# controller14.net
KiCad netlist of a schematic drawn in EAGLE
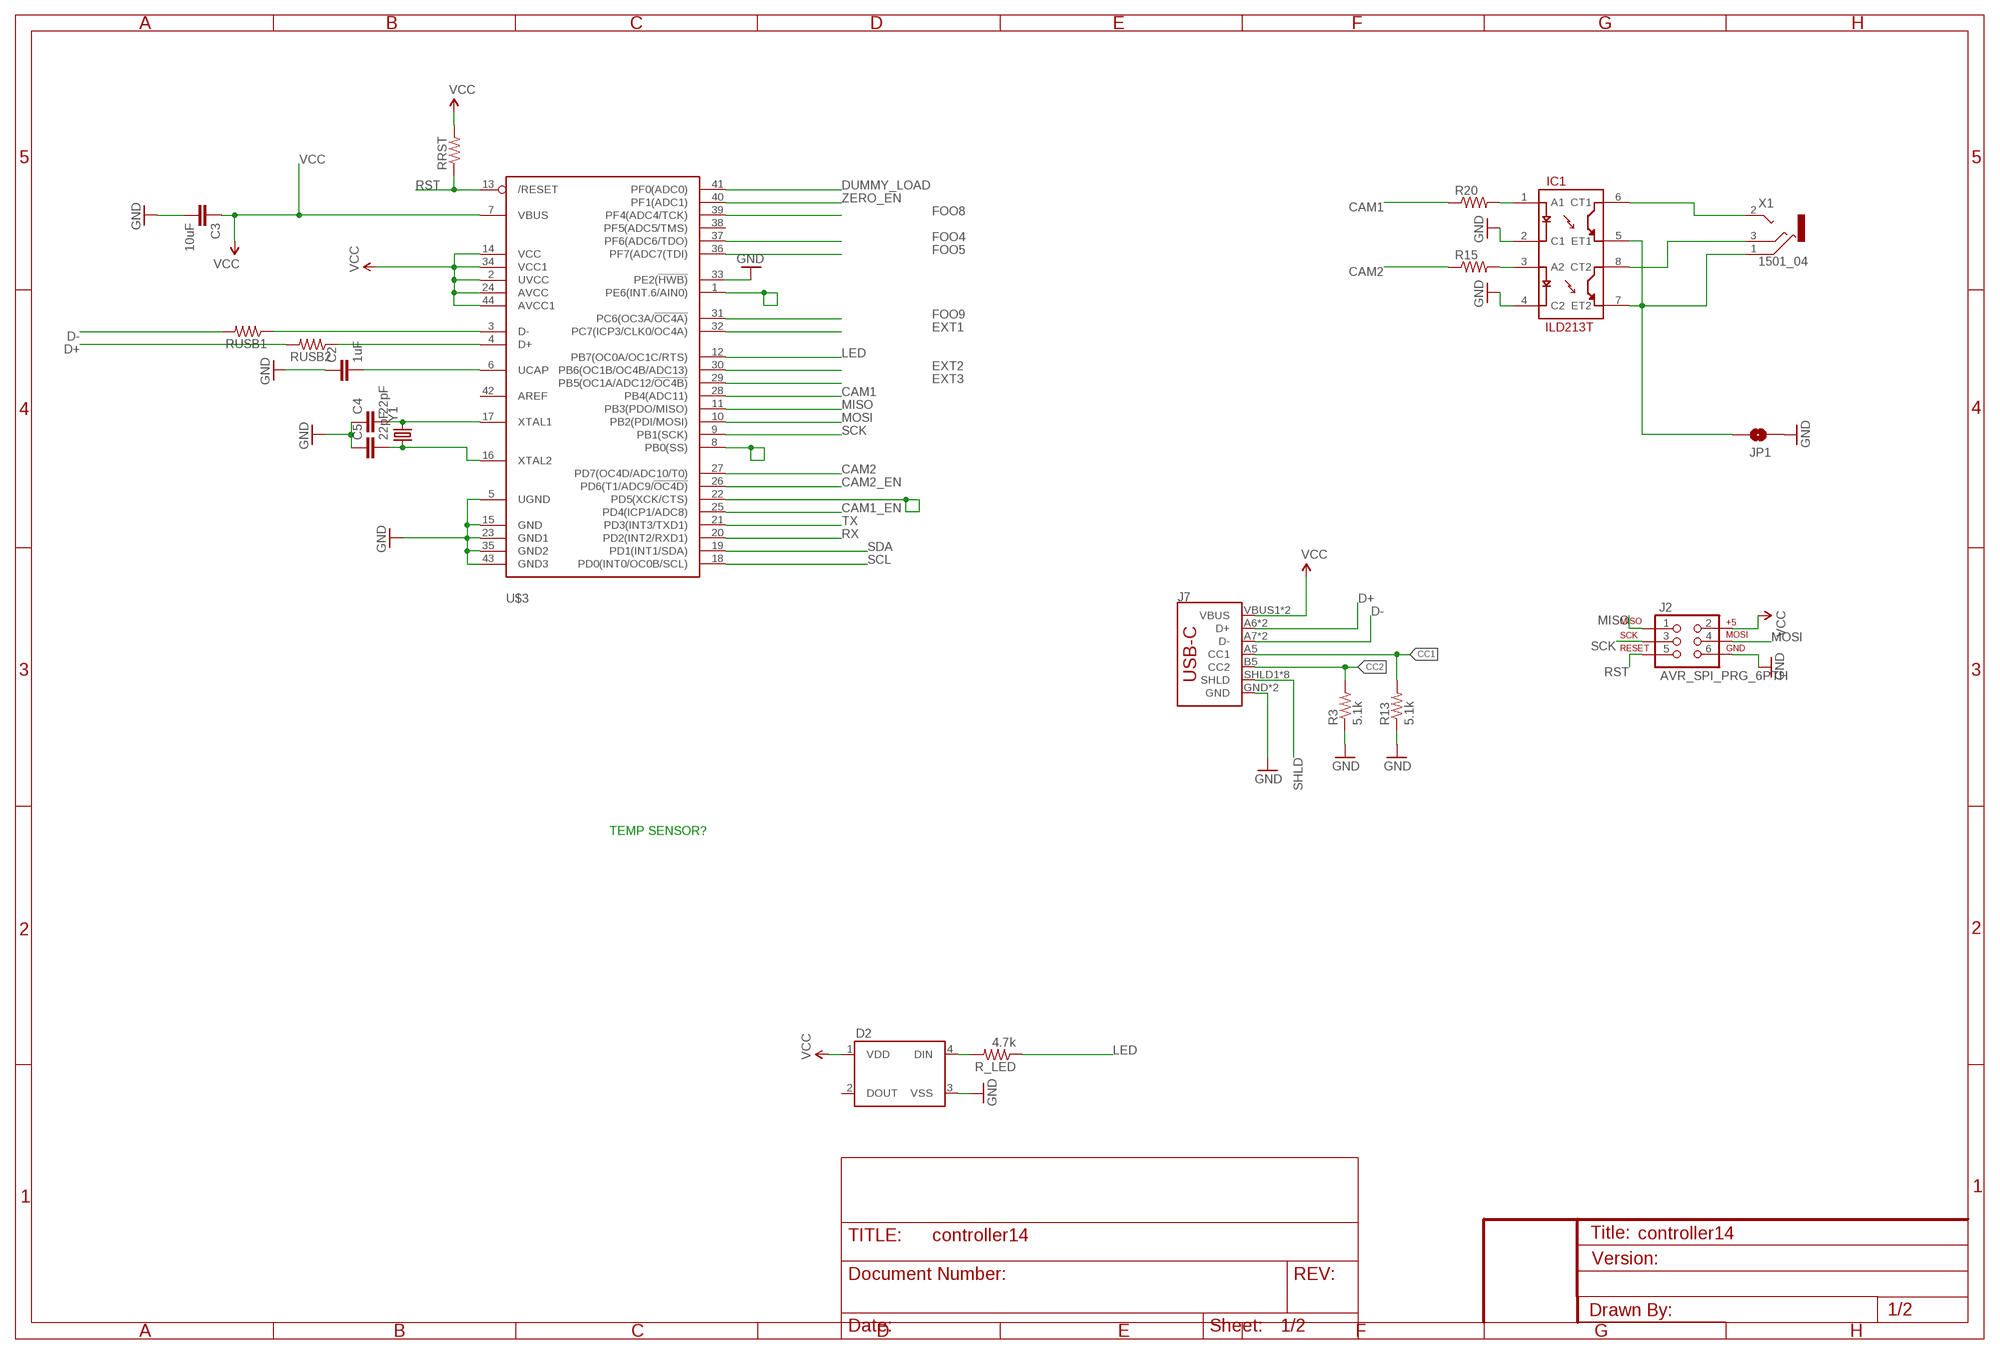
[diagram p0: schematic, sheet 1]
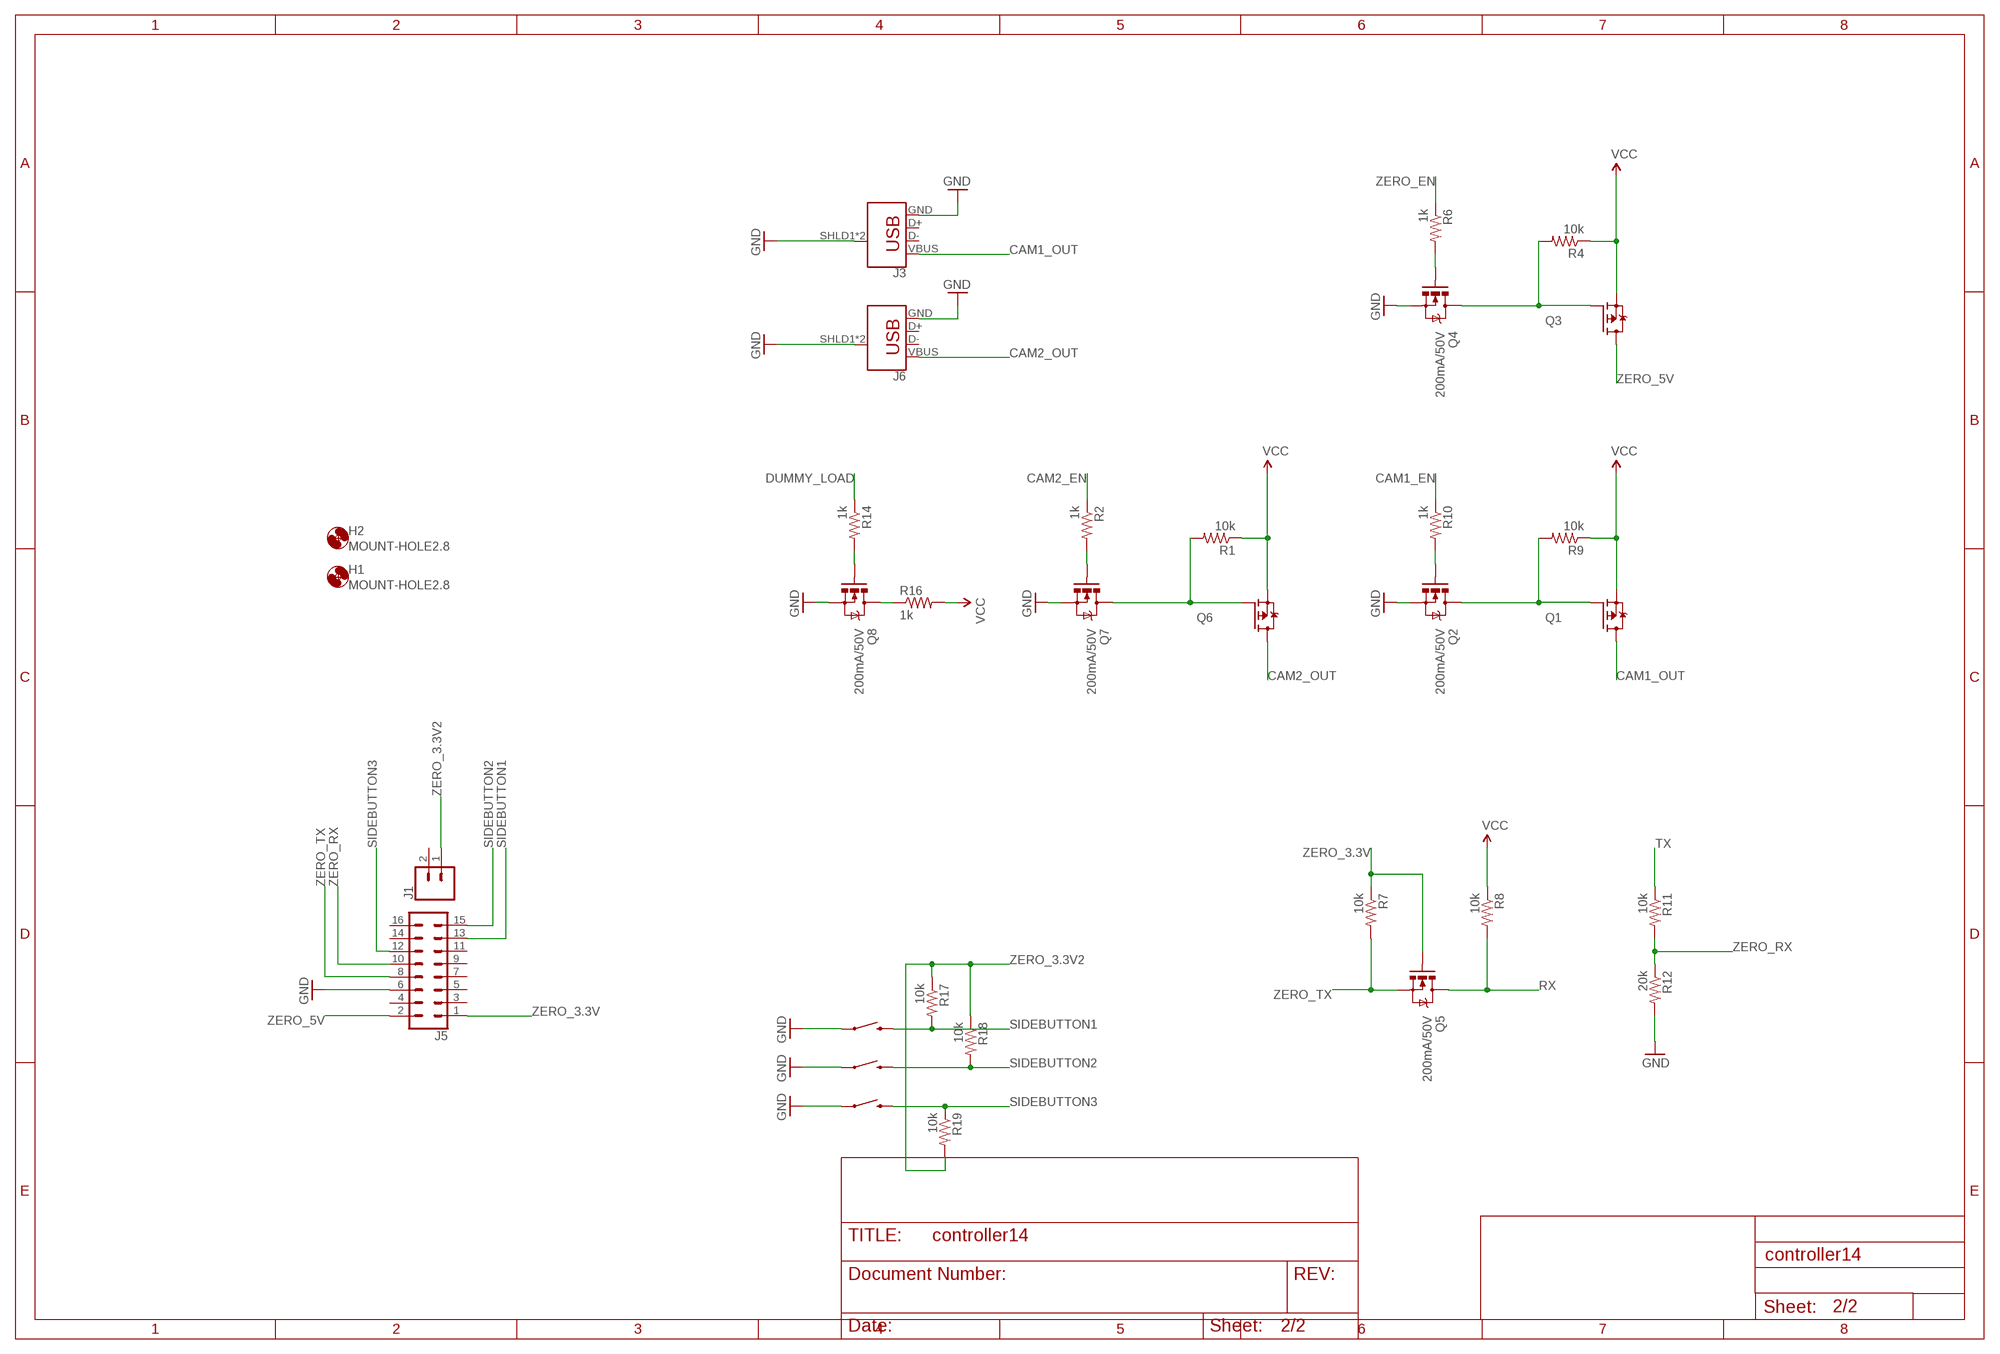
[diagram p1: schematic, sheet 2]

(export (version "E")
  (design (tool "Eeschema 10.0.6"))
  (components
    (comp (ref "C2")
      (value "1uF")
      (footprint "eagle-import:1206")
      (libsource (lib "eagle-import") (part "CAP1206"))
    )
    (comp (ref "C3")
      (value "10uF")
      (footprint "eagle-import:1206")
      (libsource (lib "eagle-import") (part "SparkFun-Passives_CAP1206"))
    )
    (comp (ref "C4")
      (value "22pF")
      (footprint "eagle-import:1206")
      (libsource (lib "eagle-import") (part "SparkFun-Passives_CAP1206"))
    )
    (comp (ref "C5")
      (value "22pF")
      (footprint "eagle-import:1206")
      (libsource (lib "eagle-import") (part "SparkFun-Passives_CAP1206"))
    )
    (comp (ref "D2")
      (value "WS2812B")
      (footprint "eagle-import:WS2812B")
      (libsource (lib "eagle-import") (part "WS2812B"))
    )
    (comp (ref "IC1")
      (value "ILD213T")
      (footprint "eagle-import:SO08")
      (libsource (lib "eagle-import") (part "ILD213T"))
    )
    (comp (ref "J2")
      (value "AVR_SPI_PRG_6PTH")
      (footprint "eagle-import:2X3")
      (libsource (lib "eagle-import") (part "AVR_SPI_PRG_6PTH"))
    )
    (comp (ref "J7")
      (value "USB_C16PIN")
      (footprint "eagle-import:USB-C-16P")
      (libsource (lib "eagle-import") (part "USB_C16PIN"))
    )
    (comp (ref "JP1")
      (value "JUMPER-PAD-2-NOYES_SILK")
      (footprint "eagle-import:PAD-JUMPER-2-NO_YES_SILK")
      (libsource (lib "eagle-import") (part "JUMPER-PAD-2-NOYES_SILK"))
    )
    (comp (ref "R3")
      (value "5.1k")
      (footprint "eagle-import:1206")
      (libsource (lib "eagle-import") (part "RESISTOR1206"))
    )
    (comp (ref "R13")
      (value "5.1k")
      (footprint "eagle-import:1206")
      (libsource (lib "eagle-import") (part "RESISTOR1206"))
    )
    (comp (ref "R15")
      (value "RESISTOR1206")
      (footprint "eagle-import:1206")
      (libsource (lib "eagle-import") (part "RESISTOR1206"))
    )
    (comp (ref "R20")
      (value "RESISTOR1206")
      (footprint "eagle-import:1206")
      (libsource (lib "eagle-import") (part "RESISTOR1206"))
    )
    (comp (ref "RRST")
      (value "RESISTOR1206")
      (footprint "eagle-import:1206")
      (libsource (lib "eagle-import") (part "RESISTOR1206"))
    )
    (comp (ref "RUSB1")
      (value "RESISTOR1206")
      (footprint "eagle-import:1206")
      (libsource (lib "eagle-import") (part "RESISTOR1206"))
    )
    (comp (ref "RUSB2")
      (value "RESISTOR1206")
      (footprint "eagle-import:1206")
      (libsource (lib "eagle-import") (part "RESISTOR1206"))
    )
    (comp (ref "R_LED")
      (value "4.7k")
      (footprint "eagle-import:1206")
      (libsource (lib "eagle-import") (part "SparkFun-Resistors_RESISTOR1206"))
    )
    (comp (ref "U$3")
      (value "ATMEGA32U4-AU")
      (footprint "eagle-import:TQFP44")
      (libsource (lib "eagle-import") (part "ATMEGA32U4-AU"))
    )
    (comp (ref "X1")
      (value "1501_04")
      (footprint "eagle-import:1501_05")
      (libsource (lib "eagle-import") (part "1501_04"))
    )
    (comp (ref "Y1")
      (value "CRYSTALCRYSTAL-SMD-5X3-16MHZ")
      (footprint "eagle-import:CRYSTAL-SMD-5X3")
      (libsource (lib "eagle-import") (part "CRYSTALCRYSTAL-SMD-5X3-16MHZ"))
    )
    (comp (ref "H1")
      (value "MOUNT-HOLE2.8")
      (footprint "eagle-import:2,8")
      (libsource (lib "eagle-import") (part "MOUNT-HOLE2.8"))
    )
    (comp (ref "H2")
      (value "MOUNT-HOLE2.8")
      (footprint "eagle-import:2,8")
      (libsource (lib "eagle-import") (part "MOUNT-HOLE2.8"))
    )
    (comp (ref "J1")
      (value "CONN_02")
      (footprint "eagle-import:1X02")
      (libsource (lib "eagle-import") (part "CONN_02"))
    )
    (comp (ref "J3")
      (value "USB_A_SMT_FEMALE")
      (footprint "eagle-import:USB-A-S-SILK-FEMALE")
      (libsource (lib "eagle-import") (part "USB_A_SMT_FEMALE"))
    )
    (comp (ref "J5")
      (value "CONN_08X2")
      (footprint "eagle-import:2X8")
      (libsource (lib "eagle-import") (part "CONN_08X2"))
    )
    (comp (ref "J6")
      (value "USB_A_SMT_FEMALE")
      (footprint "eagle-import:USB-A-S-SILK-FEMALE")
      (libsource (lib "eagle-import") (part "USB_A_SMT_FEMALE"))
    )
    (comp (ref "Q1")
      (value "FDD4141TO252")
      (footprint "eagle-import:TO252")
      (libsource (lib "eagle-import") (part "FDD4141TO252"))
    )
    (comp (ref "Q2")
      (value "200mA/50V")
      (footprint "eagle-import:SOT23-3")
      (libsource (lib "eagle-import") (part "MOSFET-NCHANNELBSS138"))
    )
    (comp (ref "Q3")
      (value "FDD4141TO252")
      (footprint "eagle-import:TO252")
      (libsource (lib "eagle-import") (part "FDD4141TO252"))
    )
    (comp (ref "Q4")
      (value "200mA/50V")
      (footprint "eagle-import:SOT23-3")
      (libsource (lib "eagle-import") (part "MOSFET-NCHANNELBSS138"))
    )
    (comp (ref "Q5")
      (value "200mA/50V")
      (footprint "eagle-import:SOT23-3")
      (libsource (lib "eagle-import") (part "MOSFET-NCHANNELBSS138"))
    )
    (comp (ref "Q6")
      (value "FDD4141TO252")
      (footprint "eagle-import:TO252")
      (libsource (lib "eagle-import") (part "FDD4141TO252"))
    )
    (comp (ref "Q7")
      (value "200mA/50V")
      (footprint "eagle-import:SOT23-3")
      (libsource (lib "eagle-import") (part "MOSFET-NCHANNELBSS138"))
    )
    (comp (ref "Q8")
      (value "200mA/50V")
      (footprint "eagle-import:SOT23-3")
      (libsource (lib "eagle-import") (part "MOSFET-NCHANNELBSS138"))
    )
    (comp (ref "R1")
      (value "10k")
      (footprint "eagle-import:1206")
      (libsource (lib "eagle-import") (part "SparkFun-Resistors_RESISTOR1206"))
    )
    (comp (ref "R2")
      (value "1k")
      (footprint "eagle-import:1206")
      (libsource (lib "eagle-import") (part "SparkFun-Resistors_RESISTOR1206"))
    )
    (comp (ref "R4")
      (value "10k")
      (footprint "eagle-import:1206")
      (libsource (lib "eagle-import") (part "SparkFun-Resistors_RESISTOR1206"))
    )
    (comp (ref "R6")
      (value "1k")
      (footprint "eagle-import:1206")
      (libsource (lib "eagle-import") (part "SparkFun-Resistors_RESISTOR1206"))
    )
    (comp (ref "R7")
      (value "10k")
      (footprint "eagle-import:1206")
      (libsource (lib "eagle-import") (part "SparkFun-Resistors_RESISTOR1206"))
    )
    (comp (ref "R8")
      (value "10k")
      (footprint "eagle-import:1206")
      (libsource (lib "eagle-import") (part "SparkFun-Resistors_RESISTOR1206"))
    )
    (comp (ref "R9")
      (value "10k")
      (footprint "eagle-import:1206")
      (libsource (lib "eagle-import") (part "SparkFun-Resistors_RESISTOR1206"))
    )
    (comp (ref "R10")
      (value "1k")
      (footprint "eagle-import:1206")
      (libsource (lib "eagle-import") (part "SparkFun-Resistors_RESISTOR1206"))
    )
    (comp (ref "R11")
      (value "10k")
      (footprint "eagle-import:1206")
      (libsource (lib "eagle-import") (part "SparkFun-Resistors_RESISTOR1206"))
    )
    (comp (ref "R12")
      (value "20k")
      (footprint "eagle-import:1206")
      (libsource (lib "eagle-import") (part "SparkFun-Resistors_RESISTOR1206"))
    )
    (comp (ref "R14")
      (value "1k")
      (footprint "eagle-import:1206")
      (libsource (lib "eagle-import") (part "SparkFun-Resistors_RESISTOR1206"))
    )
    (comp (ref "R16")
      (value "1k")
      (footprint "eagle-import:1206")
      (libsource (lib "eagle-import") (part "SparkFun-Resistors_RESISTOR1206"))
    )
    (comp (ref "R17")
      (value "10k")
      (footprint "eagle-import:1206")
      (libsource (lib "eagle-import") (part "SparkFun-Resistors_RESISTOR1206"))
    )
    (comp (ref "R18")
      (value "10k")
      (footprint "eagle-import:1206")
      (libsource (lib "eagle-import") (part "SparkFun-Resistors_RESISTOR1206"))
    )
    (comp (ref "R19")
      (value "10k")
      (footprint "eagle-import:1206")
      (libsource (lib "eagle-import") (part "SparkFun-Resistors_RESISTOR1206"))
    )
    (comp (ref "S3")
      (value "MOMENTARY-SWITCH-SPST-PTH-RIGHT-ANGLE-KIT")
      (footprint "eagle-import:TACTILE_SWITCH_PTH_RIGHT_ANGLE_KIT")
      (libsource (lib "eagle-import") (part "MOMENTARY-SWITCH-SPST-PTH-RIGHT-ANGLE-KIT"))
    )
    (comp (ref "S4")
      (value "MOMENTARY-SWITCH-SPST-PTH-RIGHT-ANGLE-KIT")
      (footprint "eagle-import:TACTILE_SWITCH_PTH_RIGHT_ANGLE_KIT")
      (libsource (lib "eagle-import") (part "MOMENTARY-SWITCH-SPST-PTH-RIGHT-ANGLE-KIT"))
    )
    (comp (ref "S5")
      (value "MOMENTARY-SWITCH-SPST-PTH-RIGHT-ANGLE-KIT")
      (footprint "eagle-import:TACTILE_SWITCH_PTH_RIGHT_ANGLE_KIT")
      (libsource (lib "eagle-import") (part "MOMENTARY-SWITCH-SPST-PTH-RIGHT-ANGLE-KIT"))
    )
  )
  (nets
    (net (code "1") (name "CAM1") (class "Default")
      (node (ref "R20") (pin "1") (pinfunction "1_1") (pintype "passive"))
      (node (ref "U$3") (pin "28") (pinfunction "PB4(ADC11)_28") (pintype "bidirectional"))
    )
    (net (code "2") (name "CAM1_EN") (class "Default")
      (node (ref "R10") (pin "1") (pinfunction "1_1") (pintype "passive"))
      (node (ref "U$3") (pin "25") (pinfunction "PD4(ICP1/ADC8)_25") (pintype "bidirectional"))
    )
    (net (code "3") (name "CAM1_OUT") (class "Default")
      (node (ref "J3") (pin "VBUS") (pinfunction "VBUS_VBUS") (pintype "power_in"))
      (node (ref "Q1") (pin "3") (pinfunction "D_3") (pintype "passive"))
    )
    (net (code "4") (name "CAM2") (class "Default")
      (node (ref "R15") (pin "1") (pinfunction "1_1") (pintype "passive"))
      (node (ref "U$3") (pin "27") (pinfunction "PD7(OC4D/ADC10/T0)_27") (pintype "bidirectional"))
    )
    (net (code "5") (name "CAM2_EN") (class "Default")
      (node (ref "R2") (pin "1") (pinfunction "1_1") (pintype "passive"))
      (node (ref "U$3") (pin "26") (pinfunction "PD6(T1/ADC9/~{OC4D})_26") (pintype "bidirectional"))
    )
    (net (code "6") (name "CAM2_OUT") (class "Default")
      (node (ref "J6") (pin "VBUS") (pinfunction "VBUS_VBUS") (pintype "power_in"))
      (node (ref "Q6") (pin "3") (pinfunction "D_3") (pintype "passive"))
    )
    (net (code "7") (name "CC1") (class "Default")
      (node (ref "J7") (pin "A5") (pinfunction "CC1_A5") (pintype "bidirectional"))
      (node (ref "R13") (pin "2") (pinfunction "2_2") (pintype "passive"))
    )
    (net (code "8") (name "CC2") (class "Default")
      (node (ref "J7") (pin "B5") (pinfunction "CC2_B5") (pintype "bidirectional"))
      (node (ref "R3") (pin "2") (pinfunction "2_2") (pintype "passive"))
    )
    (net (code "9") (name "D+") (class "Default")
      (node (ref "J7") (pin "A6") (pinfunction "D+_A6") (pintype "bidirectional"))
      (node (ref "J7") (pin "B6") (pinfunction "D+_B6") (pintype "bidirectional"))
      (node (ref "RUSB2") (pin "2") (pinfunction "2_2") (pintype "passive"))
    )
    (net (code "10") (name "D-") (class "Default")
      (node (ref "J7") (pin "A7") (pinfunction "D-_A7") (pintype "bidirectional"))
      (node (ref "J7") (pin "B7") (pinfunction "D-_B7") (pintype "bidirectional"))
      (node (ref "RUSB1") (pin "2") (pinfunction "2_2") (pintype "passive"))
    )
    (net (code "11") (name "DUMMY_LOAD") (class "Default")
      (node (ref "R14") (pin "1") (pinfunction "1_1") (pintype "passive"))
      (node (ref "U$3") (pin "41") (pinfunction "PF0(ADC0)_41") (pintype "bidirectional"))
    )
    (net (code "12") (name "EXT1") (class "Default")
      (node (ref "U$3") (pin "32") (pinfunction "PC7(ICP3/CLK0/OC4A)_32") (pintype "bidirectional"))
    )
    (net (code "13") (name "EXT2") (class "Default")
      (node (ref "U$3") (pin "30") (pinfunction "PB6(OC1B/OC4B/ADC13)_30") (pintype "bidirectional"))
    )
    (net (code "14") (name "EXT3") (class "Default")
      (node (ref "U$3") (pin "29") (pinfunction "PB5(OC1A/ADC12/~{OC4B})_29") (pintype "bidirectional"))
    )
    (net (code "15") (name "FOO4") (class "Default")
      (node (ref "U$3") (pin "37") (pinfunction "PF6(ADC6/TDO)_37") (pintype "bidirectional"))
    )
    (net (code "16") (name "FOO5") (class "Default")
      (node (ref "U$3") (pin "36") (pinfunction "PF7(ADC7(TDI)_36") (pintype "bidirectional"))
    )
    (net (code "17") (name "FOO8") (class "Default")
      (node (ref "U$3") (pin "39") (pinfunction "PF4(ADC4/TCK)_39") (pintype "bidirectional"))
    )
    (net (code "18") (name "FOO9") (class "Default")
      (node (ref "U$3") (pin "31") (pinfunction "PC6(OC3A/~{OC4A})_31") (pintype "bidirectional"))
    )
    (net (code "19") (name "GND") (class "Default")
      (node (ref "C2") (pin "1") (pinfunction "1_1") (pintype "passive"))
      (node (ref "C3") (pin "2") (pinfunction "2_2") (pintype "passive"))
      (node (ref "C4") (pin "1") (pinfunction "1_1") (pintype "passive"))
      (node (ref "C5") (pin "1") (pinfunction "1_1") (pintype "passive"))
      (node (ref "D2") (pin "3") (pinfunction "VSS_3") (pintype "power_in"))
      (node (ref "IC1") (pin "2") (pinfunction "C1_2") (pintype "bidirectional"))
      (node (ref "IC1") (pin "4") (pinfunction "C2_4") (pintype "bidirectional"))
      (node (ref "J2") (pin "6") (pinfunction "6_6") (pintype "passive"))
      (node (ref "J3") (pin "GND") (pinfunction "GND_GND") (pintype "power_in"))
      (node (ref "J3") (pin "SHLD1") (pinfunction "SHIELD_SHLD1") (pintype "bidirectional"))
      (node (ref "J3") (pin "SHLD2") (pinfunction "SHIELD_SHLD2") (pintype "bidirectional"))
      (node (ref "J5") (pin "6") (pinfunction "6_6") (pintype "passive"))
      (node (ref "J6") (pin "GND") (pinfunction "GND_GND") (pintype "power_in"))
      (node (ref "J6") (pin "SHLD1") (pinfunction "SHIELD_SHLD1") (pintype "bidirectional"))
      (node (ref "J6") (pin "SHLD2") (pinfunction "SHIELD_SHLD2") (pintype "bidirectional"))
      (node (ref "J7") (pin "GND") (pinfunction "GND_GND") (pintype "bidirectional"))
      (node (ref "J7") (pin "GND2") (pinfunction "GND_GND2") (pintype "bidirectional"))
      (node (ref "JP1") (pin "1") (pinfunction "1_1") (pintype "passive"))
      (node (ref "Q2") (pin "2") (pinfunction "S_2") (pintype "passive"))
      (node (ref "Q4") (pin "2") (pinfunction "S_2") (pintype "passive"))
      (node (ref "Q7") (pin "2") (pinfunction "S_2") (pintype "passive"))
      (node (ref "Q8") (pin "2") (pinfunction "S_2") (pintype "passive"))
      (node (ref "R12") (pin "2") (pinfunction "2_2") (pintype "passive"))
      (node (ref "R13") (pin "1") (pinfunction "1_1") (pintype "passive"))
      (node (ref "R3") (pin "1") (pinfunction "1_1") (pintype "passive"))
      (node (ref "S3") (pin "1") (pinfunction "1_1") (pintype "passive"))
      (node (ref "S4") (pin "1") (pinfunction "1_1") (pintype "passive"))
      (node (ref "S5") (pin "1") (pinfunction "1_1") (pintype "passive"))
      (node (ref "U$3") (pin "15") (pinfunction "GND_15") (pintype "bidirectional"))
      (node (ref "U$3") (pin "23") (pinfunction "GND1_23") (pintype "bidirectional"))
      (node (ref "U$3") (pin "33") (pinfunction "PE2(~{HWB})_33") (pintype "bidirectional"))
      (node (ref "U$3") (pin "35") (pinfunction "GND2_35") (pintype "bidirectional"))
      (node (ref "U$3") (pin "43") (pinfunction "GND3_43") (pintype "bidirectional"))
      (node (ref "U$3") (pin "5") (pinfunction "UGND_5") (pintype "bidirectional"))
    )
    (net (code "20") (name "LED") (class "Default")
      (node (ref "R_LED") (pin "1") (pinfunction "1_1") (pintype "passive"))
      (node (ref "U$3") (pin "12") (pinfunction "PB7(OC0A/OC1C/RTS)_12") (pintype "bidirectional"))
    )
    (net (code "21") (name "MISO") (class "Default")
      (node (ref "J2") (pin "1") (pinfunction "1_1") (pintype "passive"))
      (node (ref "U$3") (pin "11") (pinfunction "PB3(PDO/MISO)_11") (pintype "bidirectional"))
    )
    (net (code "22") (name "MOSI") (class "Default")
      (node (ref "J2") (pin "4") (pinfunction "4_4") (pintype "passive"))
      (node (ref "U$3") (pin "10") (pinfunction "PB2(PDI/MOSI)_10") (pintype "bidirectional"))
    )
    (net (code "23") (name "Net-(D2-DIN)") (class "Default")
      (node (ref "D2") (pin "4") (pinfunction "DIN_4") (pintype "input"))
      (node (ref "R_LED") (pin "2") (pinfunction "2_2") (pintype "passive"))
    )
    (net (code "24") (name "Net-(IC1-A1)") (class "Default")
      (node (ref "IC1") (pin "1") (pinfunction "A1_1") (pintype "bidirectional"))
      (node (ref "R20") (pin "2") (pinfunction "2_2") (pintype "passive"))
    )
    (net (code "25") (name "Net-(IC1-A2)") (class "Default")
      (node (ref "IC1") (pin "3") (pinfunction "A2_3") (pintype "bidirectional"))
      (node (ref "R15") (pin "2") (pinfunction "2_2") (pintype "passive"))
    )
    (net (code "26") (name "Net-(IC1-CT1)") (class "Default")
      (node (ref "IC1") (pin "6") (pinfunction "CT1_6") (pintype "bidirectional"))
      (node (ref "X1") (pin "2") (pinfunction "2_2") (pintype "passive"))
    )
    (net (code "27") (name "Net-(IC1-CT2)") (class "Default")
      (node (ref "IC1") (pin "8") (pinfunction "CT2_8") (pintype "bidirectional"))
      (node (ref "X1") (pin "3") (pinfunction "3_3") (pintype "passive"))
    )
    (net (code "28") (name "Net-(IC1-ET1)") (class "Default")
      (node (ref "IC1") (pin "5") (pinfunction "ET1_5") (pintype "bidirectional"))
      (node (ref "IC1") (pin "7") (pinfunction "ET2_7") (pintype "bidirectional"))
      (node (ref "JP1") (pin "2") (pinfunction "2_2") (pintype "passive"))
      (node (ref "X1") (pin "1") (pinfunction "1_1") (pintype "passive"))
    )
    (net (code "29") (name "Net-(Q1-G)") (class "Default")
      (node (ref "Q1") (pin "1") (pinfunction "G_1") (pintype "passive"))
      (node (ref "Q2") (pin "3") (pinfunction "D_3") (pintype "passive"))
      (node (ref "R9") (pin "2") (pinfunction "2_2") (pintype "passive"))
    )
    (net (code "30") (name "Net-(Q2-G)") (class "Default")
      (node (ref "Q2") (pin "1") (pinfunction "G_1") (pintype "passive"))
      (node (ref "R10") (pin "2") (pinfunction "2_2") (pintype "passive"))
    )
    (net (code "31") (name "Net-(Q3-G)") (class "Default")
      (node (ref "Q3") (pin "1") (pinfunction "G_1") (pintype "passive"))
      (node (ref "Q4") (pin "3") (pinfunction "D_3") (pintype "passive"))
      (node (ref "R4") (pin "2") (pinfunction "2_2") (pintype "passive"))
    )
    (net (code "32") (name "Net-(Q4-G)") (class "Default")
      (node (ref "Q4") (pin "1") (pinfunction "G_1") (pintype "passive"))
      (node (ref "R6") (pin "2") (pinfunction "2_2") (pintype "passive"))
    )
    (net (code "33") (name "Net-(Q6-G)") (class "Default")
      (node (ref "Q6") (pin "1") (pinfunction "G_1") (pintype "passive"))
      (node (ref "Q7") (pin "3") (pinfunction "D_3") (pintype "passive"))
      (node (ref "R1") (pin "2") (pinfunction "2_2") (pintype "passive"))
    )
    (net (code "34") (name "Net-(Q7-G)") (class "Default")
      (node (ref "Q7") (pin "1") (pinfunction "G_1") (pintype "passive"))
      (node (ref "R2") (pin "2") (pinfunction "2_2") (pintype "passive"))
    )
    (net (code "35") (name "Net-(Q8-D)") (class "Default")
      (node (ref "Q8") (pin "3") (pinfunction "D_3") (pintype "passive"))
      (node (ref "R16") (pin "1") (pinfunction "1_1") (pintype "passive"))
    )
    (net (code "36") (name "Net-(Q8-G)") (class "Default")
      (node (ref "Q8") (pin "1") (pinfunction "G_1") (pintype "passive"))
      (node (ref "R14") (pin "2") (pinfunction "2_2") (pintype "passive"))
    )
    (net (code "37") (name "Net-(U$3-D+)") (class "Default")
      (node (ref "RUSB2") (pin "1") (pinfunction "1_1") (pintype "passive"))
      (node (ref "U$3") (pin "4") (pinfunction "D+_4") (pintype "bidirectional"))
    )
    (net (code "38") (name "Net-(U$3-D-)") (class "Default")
      (node (ref "RUSB1") (pin "1") (pinfunction "1_1") (pintype "passive"))
      (node (ref "U$3") (pin "3") (pinfunction "D-_3") (pintype "bidirectional"))
    )
    (net (code "39") (name "Net-(U$3-UCAP)") (class "Default")
      (node (ref "C2") (pin "2") (pinfunction "2_2") (pintype "passive"))
      (node (ref "U$3") (pin "6") (pinfunction "UCAP_6") (pintype "bidirectional"))
    )
    (net (code "40") (name "Net-(U$3-XTAL1)") (class "Default")
      (node (ref "C4") (pin "2") (pinfunction "2_2") (pintype "passive"))
      (node (ref "U$3") (pin "17") (pinfunction "XTAL1_17") (pintype "bidirectional"))
      (node (ref "Y1") (pin "3") (pinfunction "2_3") (pintype "passive"))
    )
    (net (code "41") (name "Net-(U$3-XTAL2)") (class "Default")
      (node (ref "C5") (pin "2") (pinfunction "2_2") (pintype "passive"))
      (node (ref "U$3") (pin "16") (pinfunction "XTAL2_16") (pintype "bidirectional"))
      (node (ref "Y1") (pin "1") (pinfunction "1_1") (pintype "passive"))
    )
    (net (code "42") (name "RST") (class "Default")
      (node (ref "J2") (pin "5") (pinfunction "5_5") (pintype "passive"))
      (node (ref "RRST") (pin "1") (pinfunction "1_1") (pintype "passive"))
      (node (ref "U$3") (pin "13") (pinfunction "/RESET_13") (pintype "bidirectional"))
    )
    (net (code "43") (name "RX") (class "Default")
      (node (ref "Q5") (pin "3") (pinfunction "D_3") (pintype "passive"))
      (node (ref "R8") (pin "2") (pinfunction "2_2") (pintype "passive"))
      (node (ref "U$3") (pin "20") (pinfunction "PD2(INT2/RXD1)_20") (pintype "bidirectional"))
    )
    (net (code "44") (name "SCK") (class "Default")
      (node (ref "J2") (pin "3") (pinfunction "3_3") (pintype "passive"))
      (node (ref "U$3") (pin "9") (pinfunction "PB1(SCK)_9") (pintype "bidirectional"))
    )
    (net (code "45") (name "SCL") (class "Default")
      (node (ref "U$3") (pin "18") (pinfunction "PD0(INT0/OC0B/SCL)_18") (pintype "bidirectional"))
    )
    (net (code "46") (name "SDA") (class "Default")
      (node (ref "U$3") (pin "19") (pinfunction "PD1(INT1/SDA)_19") (pintype "bidirectional"))
    )
    (net (code "47") (name "SHLD") (class "Default")
      (node (ref "J7") (pin "SHLD1") (pinfunction "SHLD_SHLD1") (pintype "bidirectional"))
      (node (ref "J7") (pin "SHLD2") (pinfunction "SHLD_SHLD2") (pintype "bidirectional"))
      (node (ref "J7") (pin "SHLD3") (pinfunction "SHLD_SHLD3") (pintype "bidirectional"))
      (node (ref "J7") (pin "SHLD4") (pinfunction "SHLD_SHLD4") (pintype "bidirectional"))
      (node (ref "J7") (pin "SHLD5") (pinfunction "SHLD_SHLD5") (pintype "bidirectional"))
      (node (ref "J7") (pin "SHLD6") (pinfunction "SHLD_SHLD6") (pintype "bidirectional"))
      (node (ref "J7") (pin "SHLD7") (pinfunction "SHLD_SHLD7") (pintype "bidirectional"))
      (node (ref "J7") (pin "SHLD8") (pinfunction "SHLD_SHLD8") (pintype "bidirectional"))
    )
    (net (code "48") (name "SIDEBUTTON1") (class "Default")
      (node (ref "J5") (pin "13") (pinfunction "13_13") (pintype "passive"))
      (node (ref "R17") (pin "2") (pinfunction "2_2") (pintype "passive"))
      (node (ref "S5") (pin "2") (pinfunction "2_2") (pintype "passive"))
    )
    (net (code "49") (name "SIDEBUTTON2") (class "Default")
      (node (ref "J5") (pin "15") (pinfunction "15_15") (pintype "passive"))
      (node (ref "R18") (pin "2") (pinfunction "2_2") (pintype "passive"))
      (node (ref "S4") (pin "2") (pinfunction "2_2") (pintype "passive"))
    )
    (net (code "50") (name "SIDEBUTTON3") (class "Default")
      (node (ref "J5") (pin "12") (pinfunction "12_12") (pintype "passive"))
      (node (ref "R19") (pin "1") (pinfunction "1_1") (pintype "passive"))
      (node (ref "S3") (pin "2") (pinfunction "2_2") (pintype "passive"))
    )
    (net (code "51") (name "TX") (class "Default")
      (node (ref "R11") (pin "1") (pinfunction "1_1") (pintype "passive"))
      (node (ref "U$3") (pin "21") (pinfunction "PD3(INT3/TXD1)_21") (pintype "bidirectional"))
    )
    (net (code "52") (name "VCC") (class "Default")
      (node (ref "C3") (pin "1") (pinfunction "1_1") (pintype "passive"))
      (node (ref "D2") (pin "1") (pinfunction "VDD_1") (pintype "power_in"))
      (node (ref "J2") (pin "2") (pinfunction "2_2") (pintype "passive"))
      (node (ref "J7") (pin "VBUS1") (pinfunction "VBUS_VBUS1") (pintype "bidirectional"))
      (node (ref "J7") (pin "VBUS2") (pinfunction "VBUS_VBUS2") (pintype "bidirectional"))
      (node (ref "Q1") (pin "2") (pinfunction "S_2") (pintype "passive"))
      (node (ref "Q3") (pin "2") (pinfunction "S_2") (pintype "passive"))
      (node (ref "Q6") (pin "2") (pinfunction "S_2") (pintype "passive"))
      (node (ref "R1") (pin "1") (pinfunction "1_1") (pintype "passive"))
      (node (ref "R16") (pin "2") (pinfunction "2_2") (pintype "passive"))
      (node (ref "R4") (pin "1") (pinfunction "1_1") (pintype "passive"))
      (node (ref "R8") (pin "1") (pinfunction "1_1") (pintype "passive"))
      (node (ref "R9") (pin "1") (pinfunction "1_1") (pintype "passive"))
      (node (ref "RRST") (pin "2") (pinfunction "2_2") (pintype "passive"))
      (node (ref "U$3") (pin "14") (pinfunction "VCC_14") (pintype "bidirectional"))
      (node (ref "U$3") (pin "2") (pinfunction "UVCC_2") (pintype "bidirectional"))
      (node (ref "U$3") (pin "24") (pinfunction "AVCC_24") (pintype "bidirectional"))
      (node (ref "U$3") (pin "34") (pinfunction "VCC1_34") (pintype "bidirectional"))
      (node (ref "U$3") (pin "44") (pinfunction "AVCC1_44") (pintype "bidirectional"))
      (node (ref "U$3") (pin "7") (pinfunction "VBUS_7") (pintype "bidirectional"))
    )
    (net (code "53") (name "ZERO_3.3V") (class "Default")
      (node (ref "J5") (pin "1") (pinfunction "1_1") (pintype "passive"))
      (node (ref "Q5") (pin "1") (pinfunction "G_1") (pintype "passive"))
      (node (ref "R7") (pin "1") (pinfunction "1_1") (pintype "passive"))
    )
    (net (code "54") (name "ZERO_3.3V2") (class "Default")
      (node (ref "J1") (pin "1") (pinfunction "1_1") (pintype "passive"))
      (node (ref "R17") (pin "1") (pinfunction "1_1") (pintype "passive"))
      (node (ref "R18") (pin "1") (pinfunction "1_1") (pintype "passive"))
      (node (ref "R19") (pin "2") (pinfunction "2_2") (pintype "passive"))
    )
    (net (code "55") (name "ZERO_5V") (class "Default")
      (node (ref "J5") (pin "2") (pinfunction "2_2") (pintype "passive"))
      (node (ref "Q3") (pin "3") (pinfunction "D_3") (pintype "passive"))
    )
    (net (code "56") (name "ZERO_EN") (class "Default")
      (node (ref "R6") (pin "1") (pinfunction "1_1") (pintype "passive"))
      (node (ref "U$3") (pin "40") (pinfunction "PF1(ADC1)_40") (pintype "bidirectional"))
    )
    (net (code "57") (name "ZERO_RX") (class "Default")
      (node (ref "J5") (pin "10") (pinfunction "10_10") (pintype "passive"))
      (node (ref "R11") (pin "2") (pinfunction "2_2") (pintype "passive"))
      (node (ref "R12") (pin "1") (pinfunction "1_1") (pintype "passive"))
    )
    (net (code "58") (name "ZERO_TX") (class "Default")
      (node (ref "J5") (pin "8") (pinfunction "8_8") (pintype "passive"))
      (node (ref "Q5") (pin "2") (pinfunction "S_2") (pintype "passive"))
      (node (ref "R7") (pin "2") (pinfunction "2_2") (pintype "passive"))
    )
    (net (code "59") (name "unconnected-(D2-DOUT-Pad2)") (class "Default")
      (node (ref "D2") (pin "2") (pinfunction "DOUT_2") (pintype "output"))
    )
    (net (code "60") (name "unconnected-(J1-Pad2)") (class "Default")
      (node (ref "J1") (pin "2") (pinfunction "2_2") (pintype "passive"))
    )
    (net (code "61") (name "unconnected-(J3-PadD+)") (class "Default")
      (node (ref "J3") (pin "D+") (pinfunction "D+_D+") (pintype "bidirectional"))
    )
    (net (code "62") (name "unconnected-(J3-PadD-)") (class "Default")
      (node (ref "J3") (pin "D-") (pinfunction "D-_D-") (pintype "bidirectional"))
    )
    (net (code "63") (name "unconnected-(J5-Pad3)") (class "Default")
      (node (ref "J5") (pin "3") (pinfunction "3_3") (pintype "passive"))
    )
    (net (code "64") (name "unconnected-(J5-Pad4)") (class "Default")
      (node (ref "J5") (pin "4") (pinfunction "4_4") (pintype "passive"))
    )
    (net (code "65") (name "unconnected-(J5-Pad5)") (class "Default")
      (node (ref "J5") (pin "5") (pinfunction "5_5") (pintype "passive"))
    )
    (net (code "66") (name "unconnected-(J5-Pad7)") (class "Default")
      (node (ref "J5") (pin "7") (pinfunction "7_7") (pintype "passive"))
    )
    (net (code "67") (name "unconnected-(J5-Pad9)") (class "Default")
      (node (ref "J5") (pin "9") (pinfunction "9_9") (pintype "passive"))
    )
    (net (code "68") (name "unconnected-(J5-Pad11)") (class "Default")
      (node (ref "J5") (pin "11") (pinfunction "11_11") (pintype "passive"))
    )
    (net (code "69") (name "unconnected-(J5-Pad14)") (class "Default")
      (node (ref "J5") (pin "14") (pinfunction "14_14") (pintype "passive"))
    )
    (net (code "70") (name "unconnected-(J5-Pad16)") (class "Default")
      (node (ref "J5") (pin "16") (pinfunction "16_16") (pintype "passive"))
    )
    (net (code "71") (name "unconnected-(J6-PadD+)") (class "Default")
      (node (ref "J6") (pin "D+") (pinfunction "D+_D+") (pintype "bidirectional"))
    )
    (net (code "72") (name "unconnected-(J6-PadD-)") (class "Default")
      (node (ref "J6") (pin "D-") (pinfunction "D-_D-") (pintype "bidirectional"))
    )
    (net (code "73") (name "unconnected-(U$3-AREF-Pad42)") (class "Default")
      (node (ref "U$3") (pin "42") (pinfunction "AREF_42") (pintype "bidirectional"))
    )
    (net (code "74") (name "unconnected-(U$3-PB0(SS)-Pad8)") (class "Default")
      (node (ref "U$3") (pin "8") (pinfunction "PB0(SS)_8") (pintype "bidirectional"))
    )
    (net (code "75") (name "unconnected-(U$3-PD5(XCK{slash}CTS)-Pad22)") (class "Default")
      (node (ref "U$3") (pin "22") (pinfunction "PD5(XCK/CTS)_22") (pintype "bidirectional"))
    )
    (net (code "76") (name "unconnected-(U$3-PE6(INT.6{slash}AIN0)-Pad1)") (class "Default")
      (node (ref "U$3") (pin "1") (pinfunction "PE6(INT.6/AIN0)_1") (pintype "bidirectional"))
    )
    (net (code "77") (name "unconnected-(U$3-PF5(ADC5{slash}TMS)-Pad38)") (class "Default")
      (node (ref "U$3") (pin "38") (pinfunction "PF5(ADC5/TMS)_38") (pintype "bidirectional"))
    )
  )
)
